# Power_Distribution_-_Spares_1-4_5V.net
KiCad netlist of a schematic drawn in Altium Designer
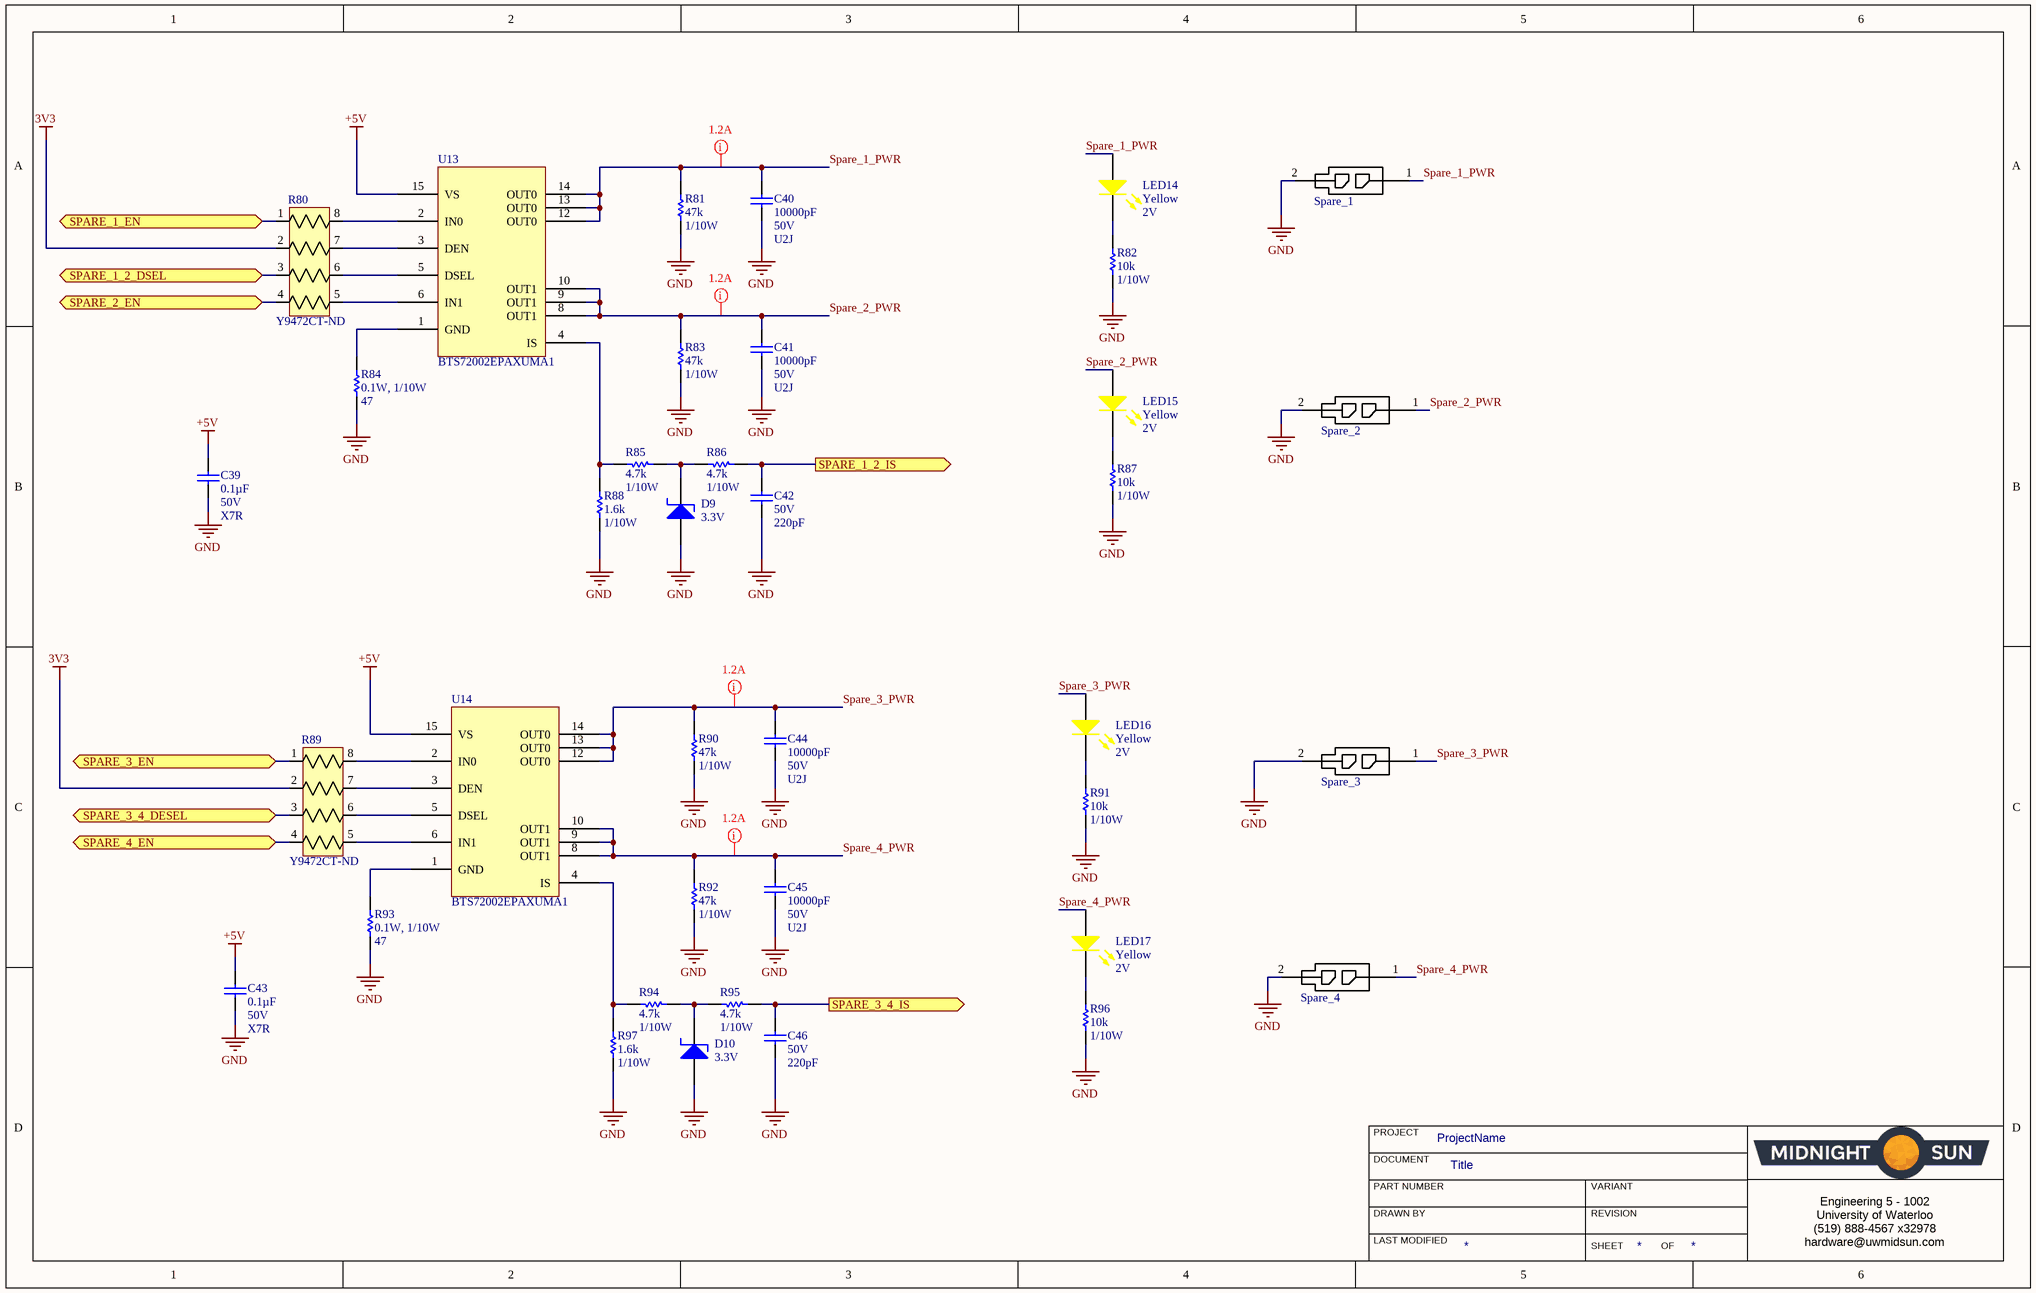
[diagram p0: Power Distribution - Spares 1-4 5V.SchDoc]

(export (version "E")
  (design (tool "Eeschema 10.0.6"))
  (components
    (comp (ref "C39")
      (value "CAP CER 0.1UF 50V 10% X7R 0603")
      (footprint "CAP, 0603")
      (description "0.10µF ±10% 50V Ceramic Capacitor X7R 0603 (1608 Metric)")
      (fields
        (field (name "TOLERANCE") "±10%")
        (field (name "CAPACITANCE") "0.1µF")
        (field (name "VOLTAGE") "50V")
        (field (name "TEMPERATURE COEFFICIENT") "X7R")
      )
      (libsource (lib "Schematic Diagrams") (part "CAP CER 0.1UF 50V 10% X7R 0603"))
    )
    (comp (ref "C40")
      (value "CAP CER 10nF 50V 5% X7R 0603")
      (footprint "CAP, 0603")
      (description "10000pF ±5% 50V Ceramic Capacitor U2J 0603 (1608 Metric)")
      (fields
        (field (name "TOLERANCE") "±5%")
        (field (name "CAPACITANCE") "10000pF")
        (field (name "VOLTAGE") "50V")
        (field (name "TEMPERATURE COEFFICIENT") "U2J")
      )
      (libsource (lib "Schematic Diagrams") (part "CAP CER 10nF 50V 5% X7R 0603"))
    )
    (comp (ref "C41")
      (value "CAP CER 10nF 50V 5% X7R 0603")
      (footprint "CAP, 0603")
      (description "10000pF ±5% 50V Ceramic Capacitor U2J 0603 (1608 Metric)")
      (fields
        (field (name "TOLERANCE") "±5%")
        (field (name "CAPACITANCE") "10000pF")
        (field (name "VOLTAGE") "50V")
        (field (name "TEMPERATURE COEFFICIENT") "U2J")
      )
      (libsource (lib "Schematic Diagrams") (part "CAP CER 10nF 50V 5% X7R 0603"))
    )
    (comp (ref "C42")
      (value "CAP CER 220PF 50V C0G/NP0 0603")
      (footprint "CAP, 0603")
      (description "220pF ±5% 50V Ceramic Capacitor C0G, NP0 0603 (1608 Metric)")
      (fields
        (field (name "MANUFACTURER") "KEMET")
        (field (name "TOLERANCE") "5%")
        (field (name "VOLTAGE RATING") "50V")
        (field (name "CAPACITANCE") "220pF")
      )
      (libsource (lib "Schematic Diagrams") (part "CAP CER 220PF 50V C0G/NP0 0603"))
    )
    (comp (ref "C43")
      (value "CAP CER 0.1UF 50V 10% X7R 0603")
      (footprint "CAP, 0603")
      (description "0.10µF ±10% 50V Ceramic Capacitor X7R 0603 (1608 Metric)")
      (fields
        (field (name "TOLERANCE") "±10%")
        (field (name "CAPACITANCE") "0.1µF")
        (field (name "VOLTAGE") "50V")
        (field (name "TEMPERATURE COEFFICIENT") "X7R")
      )
      (libsource (lib "Schematic Diagrams") (part "CAP CER 0.1UF 50V 10% X7R 0603"))
    )
    (comp (ref "C44")
      (value "CAP CER 10nF 50V 5% X7R 0603")
      (footprint "CAP, 0603")
      (description "10000pF ±5% 50V Ceramic Capacitor U2J 0603 (1608 Metric)")
      (fields
        (field (name "TOLERANCE") "±5%")
        (field (name "CAPACITANCE") "10000pF")
        (field (name "VOLTAGE") "50V")
        (field (name "TEMPERATURE COEFFICIENT") "U2J")
      )
      (libsource (lib "Schematic Diagrams") (part "CAP CER 10nF 50V 5% X7R 0603"))
    )
    (comp (ref "C45")
      (value "CAP CER 10nF 50V 5% X7R 0603")
      (footprint "CAP, 0603")
      (description "10000pF ±5% 50V Ceramic Capacitor U2J 0603 (1608 Metric)")
      (fields
        (field (name "TOLERANCE") "±5%")
        (field (name "CAPACITANCE") "10000pF")
        (field (name "VOLTAGE") "50V")
        (field (name "TEMPERATURE COEFFICIENT") "U2J")
      )
      (libsource (lib "Schematic Diagrams") (part "CAP CER 10nF 50V 5% X7R 0603"))
    )
    (comp (ref "C46")
      (value "CAP CER 220PF 50V C0G/NP0 0603")
      (footprint "CAP, 0603")
      (description "220pF ±5% 50V Ceramic Capacitor C0G, NP0 0603 (1608 Metric)")
      (fields
        (field (name "MANUFACTURER") "KEMET")
        (field (name "TOLERANCE") "5%")
        (field (name "VOLTAGE RATING") "50V")
        (field (name "CAPACITANCE") "220pF")
      )
      (libsource (lib "Schematic Diagrams") (part "CAP CER 220PF 50V C0G/NP0 0603"))
    )
    (comp (ref "D9")
      (value "DIODE ZENER 3.3V 200MW SOD323")
      (footprint "sod-323")
      (description "Zener Diode 3.3V 200mW ±5% Surface Mount SOD-323")
      (fields (field (name "VOLTAGE") "3.3V"))
      (libsource (lib "Schematic Diagrams") (part "DIODE ZENER 3.3V 200MW SOD323"))
    )
    (comp (ref "D10")
      (value "DIODE ZENER 3.3V 200MW SOD323")
      (footprint "sod-323")
      (description "Zener Diode 3.3V 200mW ±5% Surface Mount SOD-323")
      (fields (field (name "VOLTAGE") "3.3V"))
      (libsource (lib "Schematic Diagrams") (part "DIODE ZENER 3.3V 200MW SOD323"))
    )
    (comp (ref "LED14")
      (value "LED YELLOW CLEAR 2.1V 0603")
      (footprint "LED_0603")
      (description "Yellow 590nm LED Indication - Discrete 2V 0603 (1608 Metric)")
      (fields
        (field (name "MANUFACTURER") "Wurth Electronics Inc.")
        (field (name "MANUFACTURER PART NUMBER") "150060YS75000")
        (field (name "COLOR") "Yellow")
        (field (name "VOLTAGE - FORWARD (VF) (TYP)") "2V")
      )
      (libsource (lib "Schematic Diagrams") (part "LED YELLOW CLEAR 2.1V 0603"))
    )
    (comp (ref "LED15")
      (value "LED YELLOW CLEAR 2.1V 0603")
      (footprint "LED_0603")
      (description "Yellow 590nm LED Indication - Discrete 2V 0603 (1608 Metric)")
      (fields
        (field (name "MANUFACTURER") "Wurth Electronics Inc.")
        (field (name "MANUFACTURER PART NUMBER") "150060YS75000")
        (field (name "COLOR") "Yellow")
        (field (name "VOLTAGE - FORWARD (VF) (TYP)") "2V")
      )
      (libsource (lib "Schematic Diagrams") (part "LED YELLOW CLEAR 2.1V 0603"))
    )
    (comp (ref "LED16")
      (value "LED YELLOW CLEAR 2.1V 0603")
      (footprint "LED_0603")
      (description "Yellow 590nm LED Indication - Discrete 2V 0603 (1608 Metric)")
      (fields
        (field (name "MANUFACTURER") "Wurth Electronics Inc.")
        (field (name "MANUFACTURER PART NUMBER") "150060YS75000")
        (field (name "COLOR") "Yellow")
        (field (name "VOLTAGE - FORWARD (VF) (TYP)") "2V")
      )
      (libsource (lib "Schematic Diagrams") (part "LED YELLOW CLEAR 2.1V 0603"))
    )
    (comp (ref "LED17")
      (value "LED YELLOW CLEAR 2.1V 0603")
      (footprint "LED_0603")
      (description "Yellow 590nm LED Indication - Discrete 2V 0603 (1608 Metric)")
      (fields
        (field (name "MANUFACTURER") "Wurth Electronics Inc.")
        (field (name "MANUFACTURER PART NUMBER") "150060YS75000")
        (field (name "COLOR") "Yellow")
        (field (name "VOLTAGE - FORWARD (VF) (TYP)") "2V")
      )
      (libsource (lib "Schematic Diagrams") (part "LED YELLOW CLEAR 2.1V 0603"))
    )
    (comp (ref "R80")
      (value "RES ARRAY 4 RES 4.7K OHM 1206")
      (footprint "RES ARRAY 4RES 1206")
      (fields (field (name "TOLERANCE") "±5%") (field (name "SUPPLIER PART NUMBER 1") "Y9472CT-ND"))
      (libsource (lib "Schematic Diagrams") (part "RES ARRAY 4 RES 4.7K OHM 1206"))
    )
    (comp (ref "R81")
      (value "RES 47K OHM 1% 1/10W 0603")
      (footprint "RES, 0603")
      (description "47 kOhms ±1% 0.1W, 1/10W Chip Resistor 0603 (1608 Metric) Automotive AEC-Q200 Thick Film")
      (fields
        (field (name "MANUFACTURER") "Panasonic")
        (field (name "MANUFACTURER PART NUMBER") "ERJ3EKF4702V")
        (field (name "RESISTANCE") "47k")
        (field (name "POWER RATING") "1/10W")
      )
      (libsource (lib "Schematic Diagrams") (part "RES 47K OHM 1% 1/10W 0603"))
    )
    (comp (ref "R82")
      (value "RES 10K OHM 1% 1/10W 0603")
      (footprint "RES, 0603")
      (description "RES SMD 10K OHM 1% 1/10W 0603")
      (fields
        (field (name "TOLERANCE") "±1%")
        (field (name "RESISTANCE") "10k")
        (field (name "POWER") "1/10W")
      )
      (libsource (lib "Schematic Diagrams") (part "RES 10K OHM 1% 1/10W 0603"))
    )
    (comp (ref "R83")
      (value "RES 47K OHM 1% 1/10W 0603")
      (footprint "RES, 0603")
      (description "47 kOhms ±1% 0.1W, 1/10W Chip Resistor 0603 (1608 Metric) Automotive AEC-Q200 Thick Film")
      (fields
        (field (name "MANUFACTURER") "Panasonic")
        (field (name "MANUFACTURER PART NUMBER") "ERJ3EKF4702V")
        (field (name "RESISTANCE") "47k")
        (field (name "POWER RATING") "1/10W")
      )
      (libsource (lib "Schematic Diagrams") (part "RES 47K OHM 1% 1/10W 0603"))
    )
    (comp (ref "R84")
      (value "RES SMD 47 OHM 1% 1/10W 0603")
      (footprint "RES, 0603")
      (fields
        (field (name "TOLERANCE") "±1%")
        (field (name "POWER (WATTS)") "0.1W, 1/10W")
        (field (name "VALUES") "47")
      )
      (libsource (lib "Schematic Diagrams") (part "RES SMD 47 OHM 1% 1/10W 0603"))
    )
    (comp (ref "R85")
      (value "RES 4.7K OHM 1% 1/10W 0603")
      (footprint "RES, 0603")
      (description "4.7k Ohm ±1% 0.1W, 1/10W Chip Resistor 0603 (1608 Metric) Moisture Resistant Thick Film")
      (fields
        (field (name "TOLERANCE") "±1%")
        (field (name "RESISTANCE (OHMS)") "4.7k")
        (field (name "POWER (WATTS)") "1/10W")
      )
      (libsource (lib "Schematic Diagrams") (part "RES 4.7K OHM 1% 1/10W 0603"))
    )
    (comp (ref "R86")
      (value "RES 4.7K OHM 1% 1/10W 0603")
      (footprint "RES, 0603")
      (description "4.7k Ohm ±1% 0.1W, 1/10W Chip Resistor 0603 (1608 Metric) Moisture Resistant Thick Film")
      (fields
        (field (name "TOLERANCE") "±1%")
        (field (name "RESISTANCE (OHMS)") "4.7k")
        (field (name "POWER (WATTS)") "1/10W")
      )
      (libsource (lib "Schematic Diagrams") (part "RES 4.7K OHM 1% 1/10W 0603"))
    )
    (comp (ref "R87")
      (value "RES 10K OHM 1% 1/10W 0603")
      (footprint "RES, 0603")
      (description "RES SMD 10K OHM 1% 1/10W 0603")
      (fields
        (field (name "TOLERANCE") "±1%")
        (field (name "RESISTANCE") "10k")
        (field (name "POWER") "1/10W")
      )
      (libsource (lib "Schematic Diagrams") (part "RES 10K OHM 1% 1/10W 0603"))
    )
    (comp (ref "R88")
      (value "RES 1.6K OHM 1% 1/10W 0603")
      (footprint "RES, 0603")
      (description "1.6 kOhms ±1% 0.1W, 1/10W Chip Resistor 0603 (1608 Metric) Moisture Resistant Thick Film")
      (fields
        (field (name "MANUFACTURER") "Yageo")
        (field (name "MANUFACTURER PART NUMBER") "RC0603FR-071K6L")
        (field (name "RESISTANCE") "1.6k")
        (field (name "POWER RATING") "1/10W")
      )
      (libsource (lib "Schematic Diagrams") (part "RES 1.6K OHM 1% 1/10W 0603"))
    )
    (comp (ref "R89")
      (value "RES ARRAY 4 RES 4.7K OHM 1206")
      (footprint "RES ARRAY 4RES 1206")
      (fields (field (name "TOLERANCE") "±5%") (field (name "SUPPLIER PART NUMBER 1") "Y9472CT-ND"))
      (libsource (lib "Schematic Diagrams") (part "RES ARRAY 4 RES 4.7K OHM 1206"))
    )
    (comp (ref "R90")
      (value "RES 47K OHM 1% 1/10W 0603")
      (footprint "RES, 0603")
      (description "47 kOhms ±1% 0.1W, 1/10W Chip Resistor 0603 (1608 Metric) Automotive AEC-Q200 Thick Film")
      (fields
        (field (name "MANUFACTURER") "Panasonic")
        (field (name "MANUFACTURER PART NUMBER") "ERJ3EKF4702V")
        (field (name "RESISTANCE") "47k")
        (field (name "POWER RATING") "1/10W")
      )
      (libsource (lib "Schematic Diagrams") (part "RES 47K OHM 1% 1/10W 0603"))
    )
    (comp (ref "R91")
      (value "RES 10K OHM 1% 1/10W 0603")
      (footprint "RES, 0603")
      (description "RES SMD 10K OHM 1% 1/10W 0603")
      (fields
        (field (name "TOLERANCE") "±1%")
        (field (name "RESISTANCE") "10k")
        (field (name "POWER") "1/10W")
      )
      (libsource (lib "Schematic Diagrams") (part "RES 10K OHM 1% 1/10W 0603"))
    )
    (comp (ref "R92")
      (value "RES 47K OHM 1% 1/10W 0603")
      (footprint "RES, 0603")
      (description "47 kOhms ±1% 0.1W, 1/10W Chip Resistor 0603 (1608 Metric) Automotive AEC-Q200 Thick Film")
      (fields
        (field (name "MANUFACTURER") "Panasonic")
        (field (name "MANUFACTURER PART NUMBER") "ERJ3EKF4702V")
        (field (name "RESISTANCE") "47k")
        (field (name "POWER RATING") "1/10W")
      )
      (libsource (lib "Schematic Diagrams") (part "RES 47K OHM 1% 1/10W 0603"))
    )
    (comp (ref "R93")
      (value "RES SMD 47 OHM 1% 1/10W 0603")
      (footprint "RES, 0603")
      (fields
        (field (name "TOLERANCE") "±1%")
        (field (name "POWER (WATTS)") "0.1W, 1/10W")
        (field (name "VALUES") "47")
      )
      (libsource (lib "Schematic Diagrams") (part "RES SMD 47 OHM 1% 1/10W 0603"))
    )
    (comp (ref "R94")
      (value "RES 4.7K OHM 1% 1/10W 0603")
      (footprint "RES, 0603")
      (description "4.7k Ohm ±1% 0.1W, 1/10W Chip Resistor 0603 (1608 Metric) Moisture Resistant Thick Film")
      (fields
        (field (name "TOLERANCE") "±1%")
        (field (name "RESISTANCE (OHMS)") "4.7k")
        (field (name "POWER (WATTS)") "1/10W")
      )
      (libsource (lib "Schematic Diagrams") (part "RES 4.7K OHM 1% 1/10W 0603"))
    )
    (comp (ref "R95")
      (value "RES 4.7K OHM 1% 1/10W 0603")
      (footprint "RES, 0603")
      (description "4.7k Ohm ±1% 0.1W, 1/10W Chip Resistor 0603 (1608 Metric) Moisture Resistant Thick Film")
      (fields
        (field (name "TOLERANCE") "±1%")
        (field (name "RESISTANCE (OHMS)") "4.7k")
        (field (name "POWER (WATTS)") "1/10W")
      )
      (libsource (lib "Schematic Diagrams") (part "RES 4.7K OHM 1% 1/10W 0603"))
    )
    (comp (ref "R96")
      (value "RES 10K OHM 1% 1/10W 0603")
      (footprint "RES, 0603")
      (description "RES SMD 10K OHM 1% 1/10W 0603")
      (fields
        (field (name "TOLERANCE") "±1%")
        (field (name "RESISTANCE") "10k")
        (field (name "POWER") "1/10W")
      )
      (libsource (lib "Schematic Diagrams") (part "RES 10K OHM 1% 1/10W 0603"))
    )
    (comp (ref "R97")
      (value "RES 1.6K OHM 1% 1/10W 0603")
      (footprint "RES, 0603")
      (description "1.6 kOhms ±1% 0.1W, 1/10W Chip Resistor 0603 (1608 Metric) Moisture Resistant Thick Film")
      (fields
        (field (name "MANUFACTURER") "Yageo")
        (field (name "MANUFACTURER PART NUMBER") "RC0603FR-071K6L")
        (field (name "RESISTANCE") "1.6k")
        (field (name "POWER RATING") "1/10W")
      )
      (libsource (lib "Schematic Diagrams") (part "RES 1.6K OHM 1% 1/10W 0603"))
    )
    (comp (ref "Spare_1")
      (value "CONN 2POS MICRO-FIT 3mm")
      (footprint "CONN, 2POS MICRO-FIT")
      (description "Connector Header Through Hole 2 position")
      (fields (field (name "MANUFACTURER") "Molex") (field (name "MANUFACTURER PART NUMBER") "43045-0227"))
      (libsource (lib "Schematic Diagrams") (part "CONN 2POS MICRO-FIT 3mm"))
    )
    (comp (ref "Spare_2")
      (value "CONN 2POS MICRO-FIT 3mm")
      (footprint "CONN, 2POS MICRO-FIT")
      (description "Connector Header Through Hole 2 position")
      (fields (field (name "MANUFACTURER") "Molex") (field (name "MANUFACTURER PART NUMBER") "43045-0227"))
      (libsource (lib "Schematic Diagrams") (part "CONN 2POS MICRO-FIT 3mm"))
    )
    (comp (ref "Spare_3")
      (value "CONN 2POS MICRO-FIT 3mm")
      (footprint "CONN, 2POS MICRO-FIT")
      (description "Connector Header Through Hole 2 position")
      (fields (field (name "MANUFACTURER") "Molex") (field (name "MANUFACTURER PART NUMBER") "43045-0227"))
      (libsource (lib "Schematic Diagrams") (part "CONN 2POS MICRO-FIT 3mm"))
    )
    (comp (ref "Spare_4")
      (value "CONN 2POS MICRO-FIT 3mm")
      (footprint "CONN, 2POS MICRO-FIT")
      (description "Connector Header Through Hole 2 position")
      (fields (field (name "MANUFACTURER") "Molex") (field (name "MANUFACTURER PART NUMBER") "43045-0227"))
      (libsource (lib "Schematic Diagrams") (part "CONN 2POS MICRO-FIT 3mm"))
    )
    (comp (ref "U13")
      (value "IC LOAD SWITCH BTS7200-2EPA PG-TSDSO-14_1")
      (footprint "IC LOAD SWITCH PG-TSDSO-14-22")
      (description "Power Switch/Driver 1:1 N-Channel 1.2A PG-TSDSO-14-22")
      (fields
        (field (name "MANUFACTURER") "Infineon")
        (field (name "MANUFACTURER PART NUMBER") "BTS72002EPAXUMA1")
      )
      (libsource (lib "Schematic Diagrams") (part "IC LOAD SWITCH BTS7200-2EPA PG-TSDSO-14_1"))
    )
    (comp (ref "U14")
      (value "IC LOAD SWITCH BTS7200-2EPA PG-TSDSO-14_1")
      (footprint "IC LOAD SWITCH PG-TSDSO-14-22")
      (description "Power Switch/Driver 1:1 N-Channel 1.2A PG-TSDSO-14-22")
      (fields
        (field (name "MANUFACTURER") "Infineon")
        (field (name "MANUFACTURER PART NUMBER") "BTS72002EPAXUMA1")
      )
      (libsource (lib "Schematic Diagrams") (part "IC LOAD SWITCH BTS7200-2EPA PG-TSDSO-14_1"))
    )
  )
  (nets
    (net (code "1") (name "+5V") (class "Default")
      (node (ref "C39") (pin "1") (pinfunction "1_1") (pintype "passive"))
      (node (ref "C43") (pin "1") (pinfunction "1_1") (pintype "passive"))
      (node (ref "U13") (pin "15") (pinfunction "VS_15") (pintype "passive"))
      (node (ref "U14") (pin "15") (pinfunction "VS_15") (pintype "passive"))
    )
    (net (code "2") (name "/SPARE_1_2_DSEL") (class "Default")
      (node (ref "R80") (pin "3") (pinfunction "3_3") (pintype "passive"))
    )
    (net (code "3") (name "/SPARE_1_2_IS") (class "Default")
      (node (ref "C42") (pin "1") (pinfunction "1_1") (pintype "passive"))
      (node (ref "R86") (pin "1") (pinfunction "1_1") (pintype "passive"))
    )
    (net (code "4") (name "/SPARE_1_EN") (class "Default")
      (node (ref "R80") (pin "1") (pinfunction "1_1") (pintype "passive"))
    )
    (net (code "5") (name "/SPARE_2_EN") (class "Default")
      (node (ref "R80") (pin "4") (pinfunction "4_4") (pintype "passive"))
    )
    (net (code "6") (name "/SPARE_3_4_DESEL") (class "Default")
      (node (ref "R89") (pin "3") (pinfunction "3_3") (pintype "passive"))
    )
    (net (code "7") (name "/SPARE_3_4_IS") (class "Default")
      (node (ref "C46") (pin "1") (pinfunction "1_1") (pintype "passive"))
      (node (ref "R95") (pin "1") (pinfunction "1_1") (pintype "passive"))
    )
    (net (code "8") (name "/SPARE_3_EN") (class "Default")
      (node (ref "R89") (pin "1") (pinfunction "1_1") (pintype "passive"))
    )
    (net (code "9") (name "/SPARE_4_EN") (class "Default")
      (node (ref "R89") (pin "4") (pinfunction "4_4") (pintype "passive"))
    )
    (net (code "10") (name "/Spare_1_PWR") (class "Default")
      (node (ref "C40") (pin "1") (pinfunction "1_1") (pintype "passive"))
      (node (ref "LED14") (pin "1") (pinfunction "A_1") (pintype "passive"))
      (node (ref "R81") (pin "1") (pinfunction "1_1") (pintype "passive"))
      (node (ref "Spare_1") (pin "1") (pinfunction "1_1") (pintype "passive"))
      (node (ref "U13") (pin "12") (pinfunction "OUT0_12") (pintype "passive"))
      (node (ref "U13") (pin "13") (pinfunction "OUT0_13") (pintype "passive"))
      (node (ref "U13") (pin "14") (pinfunction "OUT0_14") (pintype "passive"))
    )
    (net (code "11") (name "/Spare_2_PWR") (class "Default")
      (node (ref "C41") (pin "1") (pinfunction "1_1") (pintype "passive"))
      (node (ref "LED15") (pin "1") (pinfunction "A_1") (pintype "passive"))
      (node (ref "R83") (pin "1") (pinfunction "1_1") (pintype "passive"))
      (node (ref "Spare_2") (pin "1") (pinfunction "1_1") (pintype "passive"))
      (node (ref "U13") (pin "10") (pinfunction "OUT1_10") (pintype "passive"))
      (node (ref "U13") (pin "8") (pinfunction "OUT1_8") (pintype "passive"))
      (node (ref "U13") (pin "9") (pinfunction "OUT1_9") (pintype "passive"))
    )
    (net (code "12") (name "/Spare_3_PWR") (class "Default")
      (node (ref "C44") (pin "1") (pinfunction "1_1") (pintype "passive"))
      (node (ref "LED16") (pin "1") (pinfunction "A_1") (pintype "passive"))
      (node (ref "R90") (pin "1") (pinfunction "1_1") (pintype "passive"))
      (node (ref "Spare_3") (pin "1") (pinfunction "1_1") (pintype "passive"))
      (node (ref "U14") (pin "12") (pinfunction "OUT0_12") (pintype "passive"))
      (node (ref "U14") (pin "13") (pinfunction "OUT0_13") (pintype "passive"))
      (node (ref "U14") (pin "14") (pinfunction "OUT0_14") (pintype "passive"))
    )
    (net (code "13") (name "/Spare_4_PWR") (class "Default")
      (node (ref "C45") (pin "1") (pinfunction "1_1") (pintype "passive"))
      (node (ref "LED17") (pin "1") (pinfunction "A_1") (pintype "passive"))
      (node (ref "R92") (pin "1") (pinfunction "1_1") (pintype "passive"))
      (node (ref "Spare_4") (pin "1") (pinfunction "1_1") (pintype "passive"))
      (node (ref "U14") (pin "10") (pinfunction "OUT1_10") (pintype "passive"))
      (node (ref "U14") (pin "8") (pinfunction "OUT1_8") (pintype "passive"))
      (node (ref "U14") (pin "9") (pinfunction "OUT1_9") (pintype "passive"))
    )
    (net (code "14") (name "3V3") (class "Default")
      (node (ref "R80") (pin "2") (pinfunction "2_2") (pintype "passive"))
      (node (ref "R89") (pin "2") (pinfunction "2_2") (pintype "passive"))
    )
    (net (code "15") (name "GND") (class "Default")
      (node (ref "C39") (pin "2") (pinfunction "2_2") (pintype "passive"))
      (node (ref "C40") (pin "2") (pinfunction "2_2") (pintype "passive"))
      (node (ref "C41") (pin "2") (pinfunction "2_2") (pintype "passive"))
      (node (ref "C42") (pin "2") (pinfunction "2_2") (pintype "passive"))
      (node (ref "C43") (pin "2") (pinfunction "2_2") (pintype "passive"))
      (node (ref "C44") (pin "2") (pinfunction "2_2") (pintype "passive"))
      (node (ref "C45") (pin "2") (pinfunction "2_2") (pintype "passive"))
      (node (ref "C46") (pin "2") (pinfunction "2_2") (pintype "passive"))
      (node (ref "D10") (pin "1") (pinfunction "A_1") (pintype "passive"))
      (node (ref "D9") (pin "1") (pinfunction "A_1") (pintype "passive"))
      (node (ref "R81") (pin "2") (pinfunction "2_2") (pintype "passive"))
      (node (ref "R82") (pin "2") (pinfunction "2_2") (pintype "passive"))
      (node (ref "R83") (pin "2") (pinfunction "2_2") (pintype "passive"))
      (node (ref "R84") (pin "2") (pinfunction "2_2") (pintype "passive"))
      (node (ref "R87") (pin "2") (pinfunction "2_2") (pintype "passive"))
      (node (ref "R88") (pin "2") (pinfunction "2_2") (pintype "passive"))
      (node (ref "R90") (pin "2") (pinfunction "2_2") (pintype "passive"))
      (node (ref "R91") (pin "2") (pinfunction "2_2") (pintype "passive"))
      (node (ref "R92") (pin "2") (pinfunction "2_2") (pintype "passive"))
      (node (ref "R93") (pin "2") (pinfunction "2_2") (pintype "passive"))
      (node (ref "R96") (pin "2") (pinfunction "2_2") (pintype "passive"))
      (node (ref "R97") (pin "2") (pinfunction "2_2") (pintype "passive"))
      (node (ref "Spare_1") (pin "2") (pinfunction "2_2") (pintype "passive"))
      (node (ref "Spare_2") (pin "2") (pinfunction "2_2") (pintype "passive"))
      (node (ref "Spare_3") (pin "2") (pinfunction "2_2") (pintype "passive"))
      (node (ref "Spare_4") (pin "2") (pinfunction "2_2") (pintype "passive"))
    )
    (net (code "16") (name "Net-(D9-K)") (class "Default")
      (node (ref "D9") (pin "2") (pinfunction "K_2") (pintype "passive"))
      (node (ref "R85") (pin "1") (pinfunction "1_1") (pintype "passive"))
      (node (ref "R86") (pin "2") (pinfunction "2_2") (pintype "passive"))
    )
    (net (code "17") (name "Net-(D10-K)") (class "Default")
      (node (ref "D10") (pin "2") (pinfunction "K_2") (pintype "passive"))
      (node (ref "R94") (pin "1") (pinfunction "1_1") (pintype "passive"))
      (node (ref "R95") (pin "2") (pinfunction "2_2") (pintype "passive"))
    )
    (net (code "18") (name "Net-(LED14-K)") (class "Default")
      (node (ref "LED14") (pin "2") (pinfunction "K_2") (pintype "passive"))
      (node (ref "R82") (pin "1") (pinfunction "1_1") (pintype "passive"))
    )
    (net (code "19") (name "Net-(LED15-K)") (class "Default")
      (node (ref "LED15") (pin "2") (pinfunction "K_2") (pintype "passive"))
      (node (ref "R87") (pin "1") (pinfunction "1_1") (pintype "passive"))
    )
    (net (code "20") (name "Net-(LED16-K)") (class "Default")
      (node (ref "LED16") (pin "2") (pinfunction "K_2") (pintype "passive"))
      (node (ref "R91") (pin "1") (pinfunction "1_1") (pintype "passive"))
    )
    (net (code "21") (name "Net-(LED17-K)") (class "Default")
      (node (ref "LED17") (pin "2") (pinfunction "K_2") (pintype "passive"))
      (node (ref "R96") (pin "1") (pinfunction "1_1") (pintype "passive"))
    )
    (net (code "22") (name "Net-(U13-DEN)") (class "Default")
      (node (ref "R80") (pin "7") (pinfunction "7_7") (pintype "passive"))
      (node (ref "U13") (pin "3") (pinfunction "DEN_3") (pintype "passive"))
    )
    (net (code "23") (name "Net-(U13-DSEL)") (class "Default")
      (node (ref "R80") (pin "6") (pinfunction "6_6") (pintype "passive"))
      (node (ref "U13") (pin "5") (pinfunction "DSEL_5") (pintype "passive"))
    )
    (net (code "24") (name "Net-(U13-GND)") (class "Default")
      (node (ref "R84") (pin "1") (pinfunction "1_1") (pintype "passive"))
      (node (ref "U13") (pin "1") (pinfunction "GND_1") (pintype "passive"))
    )
    (net (code "25") (name "Net-(U13-IN0)") (class "Default")
      (node (ref "R80") (pin "8") (pinfunction "8_8") (pintype "passive"))
      (node (ref "U13") (pin "2") (pinfunction "IN0_2") (pintype "passive"))
    )
    (net (code "26") (name "Net-(U13-IN1)") (class "Default")
      (node (ref "R80") (pin "5") (pinfunction "5_5") (pintype "passive"))
      (node (ref "U13") (pin "6") (pinfunction "IN1_6") (pintype "passive"))
    )
    (net (code "27") (name "Net-(U13-IS)") (class "Default")
      (node (ref "R85") (pin "2") (pinfunction "2_2") (pintype "passive"))
      (node (ref "R88") (pin "1") (pinfunction "1_1") (pintype "passive"))
      (node (ref "U13") (pin "4") (pinfunction "IS_4") (pintype "passive"))
    )
    (net (code "28") (name "Net-(U14-DEN)") (class "Default")
      (node (ref "R89") (pin "7") (pinfunction "7_7") (pintype "passive"))
      (node (ref "U14") (pin "3") (pinfunction "DEN_3") (pintype "passive"))
    )
    (net (code "29") (name "Net-(U14-DSEL)") (class "Default")
      (node (ref "R89") (pin "6") (pinfunction "6_6") (pintype "passive"))
      (node (ref "U14") (pin "5") (pinfunction "DSEL_5") (pintype "passive"))
    )
    (net (code "30") (name "Net-(U14-GND)") (class "Default")
      (node (ref "R93") (pin "1") (pinfunction "1_1") (pintype "passive"))
      (node (ref "U14") (pin "1") (pinfunction "GND_1") (pintype "passive"))
    )
    (net (code "31") (name "Net-(U14-IN0)") (class "Default")
      (node (ref "R89") (pin "8") (pinfunction "8_8") (pintype "passive"))
      (node (ref "U14") (pin "2") (pinfunction "IN0_2") (pintype "passive"))
    )
    (net (code "32") (name "Net-(U14-IN1)") (class "Default")
      (node (ref "R89") (pin "5") (pinfunction "5_5") (pintype "passive"))
      (node (ref "U14") (pin "6") (pinfunction "IN1_6") (pintype "passive"))
    )
    (net (code "33") (name "Net-(U14-IS)") (class "Default")
      (node (ref "R94") (pin "2") (pinfunction "2_2") (pintype "passive"))
      (node (ref "R97") (pin "1") (pinfunction "1_1") (pintype "passive"))
      (node (ref "U14") (pin "4") (pinfunction "IS_4") (pintype "passive"))
    )
  )
)
